# Sheet1.net
KiCad netlist of a schematic drawn in Altium Designer
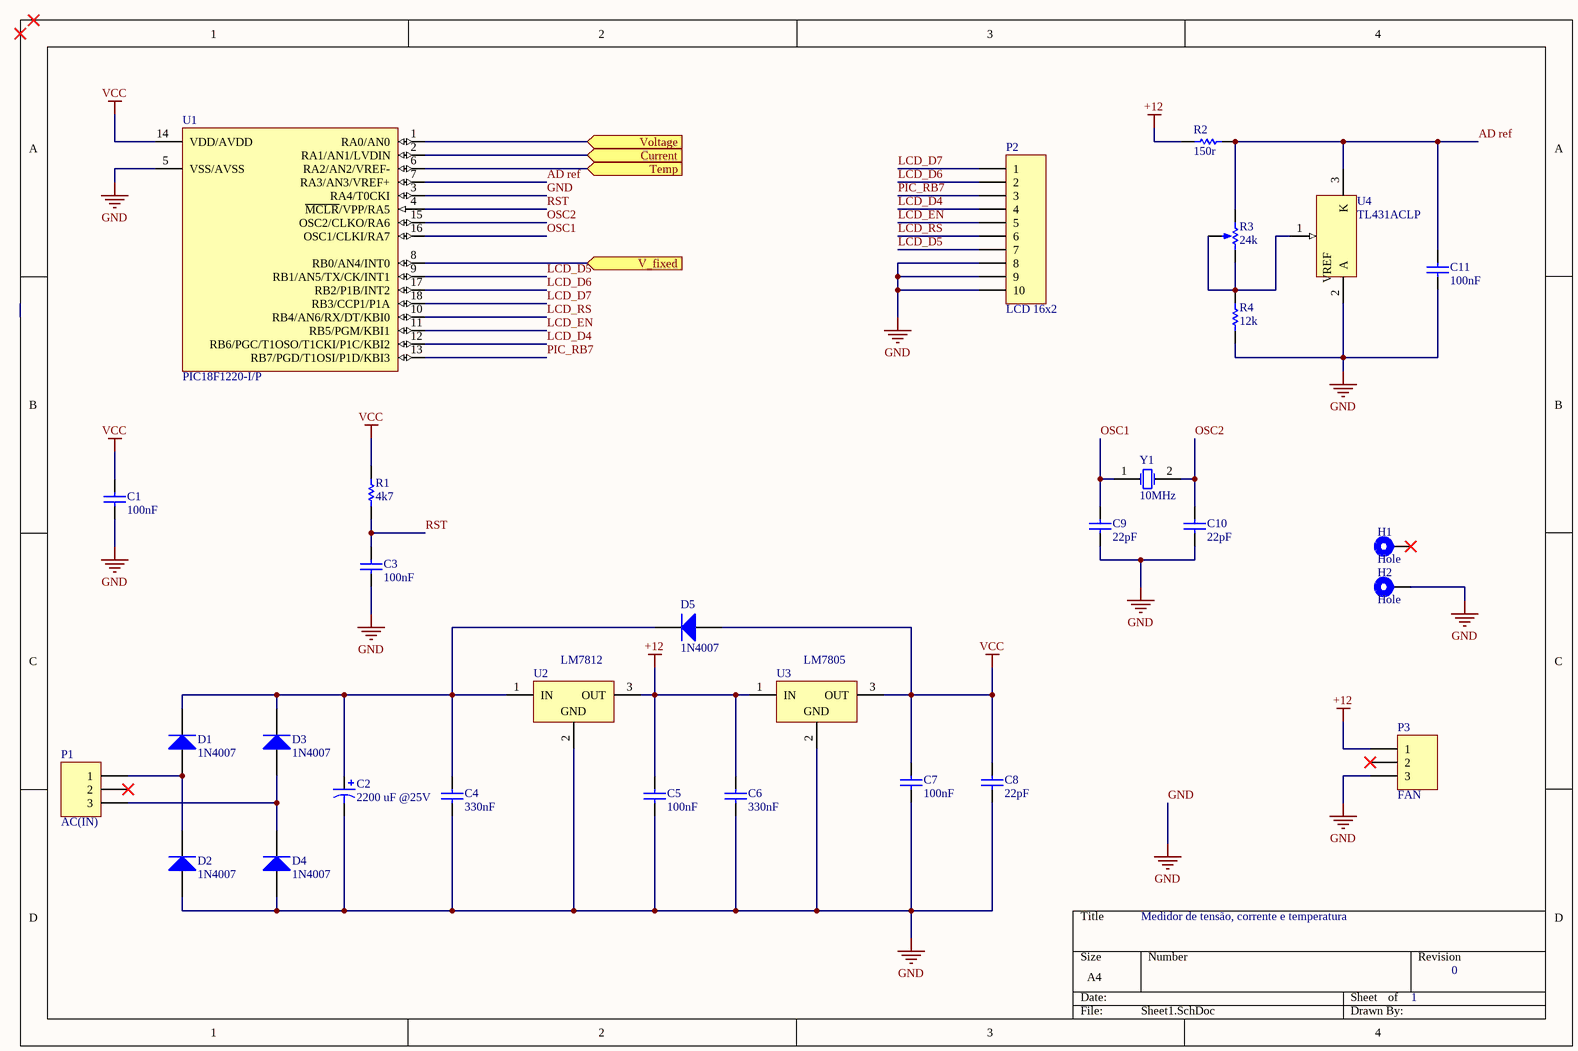
[diagram p0: Sheet1.SchDoc]

(export (version "E")
  (design (tool "Eeschema 10.0.6"))
  (components
    (comp (ref "C1")
      (value "100nF")
      (footprint "RAD-0.2")
      (description "Capacitor")
      (libsource (lib "Basic Library") (part "C"))
    )
    (comp (ref "C2")
      (value "2200 uF @25V")
      (footprint "CAPPR5-13x21")
      (description "Polarized Capacitor")
      (libsource (lib "Basic Library") (part "CP"))
    )
    (comp (ref "C3")
      (value "100nF")
      (footprint "RAD-0.2")
      (description "Capacitor")
      (libsource (lib "Basic Library") (part "C"))
    )
    (comp (ref "C4")
      (value "330nF")
      (footprint "RAD-0.2")
      (description "Capacitor")
      (libsource (lib "Basic Library") (part "C"))
    )
    (comp (ref "C5")
      (value "100nF")
      (footprint "RAD-0.2")
      (description "Capacitor")
      (libsource (lib "Basic Library") (part "C"))
    )
    (comp (ref "C6")
      (value "330nF")
      (footprint "RAD-0.2")
      (description "Capacitor")
      (libsource (lib "Basic Library") (part "C"))
    )
    (comp (ref "C7")
      (value "100nF")
      (footprint "RAD-0.2")
      (description "Capacitor")
      (libsource (lib "Basic Library") (part "C"))
    )
    (comp (ref "C8")
      (value "22pF")
      (footprint "RAD-0.2")
      (description "Capacitor")
      (libsource (lib "Basic Library") (part "C"))
    )
    (comp (ref "C9")
      (value "22pF")
      (footprint "RAD-0.2")
      (description "Capacitor")
      (libsource (lib "Basic Library") (part "C"))
    )
    (comp (ref "C10")
      (value "22pF")
      (footprint "RAD-0.2")
      (description "Capacitor")
      (libsource (lib "Basic Library") (part "C"))
    )
    (comp (ref "C11")
      (value "100nF")
      (footprint "RAD-0.2")
      (description "Capacitor")
      (libsource (lib "Basic Library") (part "C"))
    )
    (comp (ref "D1")
      (value "1N4007")
      (footprint "DIODE-1N400X")
      (description "Diode")
      (libsource (lib "Basic Library") (part "D"))
    )
    (comp (ref "D2")
      (value "1N4007")
      (footprint "DIODE-1N400X")
      (description "Diode")
      (libsource (lib "Basic Library") (part "D"))
    )
    (comp (ref "D3")
      (value "1N4007")
      (footprint "DIODE-1N400X")
      (description "Diode")
      (libsource (lib "Basic Library") (part "D"))
    )
    (comp (ref "D4")
      (value "1N4007")
      (footprint "DIODE-1N400X")
      (description "Diode")
      (libsource (lib "Basic Library") (part "D"))
    )
    (comp (ref "D5")
      (value "1N4007")
      (footprint "DO-41")
      (description "1 Amp General Purpose Rectifier")
      (fields (field (name "PUBLISHER") "Altium Limited"))
      (libsource (lib "Miscellaneous Devices") (part "Diode 1N4007"))
    )
    (comp (ref "H1") (value "Hole") (footprint "HOLE_M3") (libsource (lib "Basic Library") (part "Hole")))
    (comp (ref "H2") (value "Hole") (footprint "HOLE_M3") (libsource (lib "Basic Library") (part "Hole")))
    (comp (ref "P1")
      (value "AC(IN)")
      (footprint "HDR1X3")
      (description "Header, 3-Pin")
      (fields (field (name "PUBLISHER") "Altium Limited"))
      (libsource (lib "") (part "Header 3_1"))
    )
    (comp (ref "P2")
      (value "LCD 16x2")
      (footprint "HDR1X10")
      (description "Header, 10-Pin")
      (fields (field (name "PUBLISHER") "Altium Limited"))
      (libsource (lib "Miscellaneous Connectors") (part "Header 10"))
    )
    (comp (ref "P3")
      (value "FAN")
      (footprint "HDR1X3")
      (description "Header, 3-Pin")
      (fields (field (name "PUBLISHER") "Altium Limited"))
      (libsource (lib "Miscellaneous Connectors") (part "Header 3"))
    )
    (comp (ref "R1")
      (value "4k7")
      (footprint "AXIAL-0.4")
      (description "Resistor")
      (libsource (lib "Basic Library") (part "R"))
    )
    (comp (ref "R2")
      (value "150r")
      (footprint "AXIAL-0.4")
      (description "Resistor")
      (libsource (lib "Basic Library") (part "R"))
    )
    (comp (ref "R3")
      (value "24k")
      (footprint "VR1")
      (description "Potentiometer")
      (libsource (lib "Basic Library") (part "R Pot"))
    )
    (comp (ref "R4")
      (value "12k")
      (footprint "AXIAL-0.4")
      (description "Resistor")
      (libsource (lib "Basic Library") (part "R"))
    )
    (comp (ref "U1")
      (value "PIC18F1220-I/P")
      (footprint "PDIP300-P18")
      (fields (field (name "PUBLISHER") "Altium Limited"))
      (libsource (lib "Microchip Microcontroller 8-Bit PIC18") (part "PIC18F1220-I/P"))
    )
    (comp (ref "U2")
      (value "LM7812")
      (footprint "T03B")
      (description "Series 3-Terminal Positive Regulators, 3-pin TO-220")
      (fields
        (field (name "PARTNUMBER") "LM7808CT")
        (field (name "MANUFACTURER") "National Semiconductor")
        (field (name "PUBLISHER") "Altium Limited")
      )
      (libsource (lib "NSC Legacy") (part "LM7808CT"))
    )
    (comp (ref "U3")
      (value "LM7805")
      (footprint "T03B")
      (description "Series 3-Terminal Positive Regulators, 3-pin TO-220")
      (fields
        (field (name "PARTNUMBER") "LM7808CT")
        (field (name "MANUFACTURER") "National Semiconductor")
        (field (name "PUBLISHER") "Altium Limited")
      )
      (libsource (lib "NSC Legacy") (part "LM7808CT"))
    )
    (comp (ref "U4")
      (value "TL431ACLP")
      (footprint "LP03")
      (description "Adjustable Precision Shunt Regulator")
      (fields (field (name "PUBLISHER") "Altium Limited"))
      (libsource (lib "TI Power Mgt Voltage Regulator") (part "TL431ACLP"))
    )
    (comp (ref "Y1")
      (value "10MHz")
      (footprint "CRYSTAL-HC49S")
      (description "Crystal Oscillator")
      (libsource (lib "Basic Library") (part "XTAL"))
    )
  )
  (nets
    (net (code "1") (name "+12") (class "Default")
      (node (ref "C5") (pin "1") (pinfunction "1_1") (pintype "passive"))
      (node (ref "C6") (pin "1") (pinfunction "1_1") (pintype "passive"))
      (node (ref "P3") (pin "1") (pinfunction "1_1") (pintype "passive"))
      (node (ref "R2") (pin "1") (pinfunction "1_1") (pintype "passive"))
      (node (ref "U2") (pin "3") (pinfunction "OUT_3") (pintype "power_in"))
      (node (ref "U3") (pin "1") (pinfunction "IN_1") (pintype "power_in"))
    )
    (net (code "2") (name "/AD ref") (class "Default")
      (node (ref "C11") (pin "1") (pinfunction "1_1") (pintype "passive"))
      (node (ref "R2") (pin "2") (pinfunction "2_2") (pintype "passive"))
      (node (ref "R3") (pin "1") (pinfunction "TOP_1") (pintype "passive"))
      (node (ref "U1") (pin "7") (pinfunction "RA3/AN3/VREF+_7") (pintype "bidirectional"))
      (node (ref "U4") (pin "3") (pinfunction "K_3") (pintype "power_in"))
    )
    (net (code "3") (name "/Current") (class "Default")
      (node (ref "U1") (pin "2") (pinfunction "RA1/AN1/LVDIN_2") (pintype "bidirectional"))
    )
    (net (code "4") (name "/LCD_D4") (class "Default")
      (node (ref "P2") (pin "4") (pinfunction "4_4") (pintype "passive"))
      (node (ref "U1") (pin "12") (pinfunction "RB6/PGC/T1OSO/T1CKI/P1C/KBI2_12") (pintype "bidirectional"))
    )
    (net (code "5") (name "/LCD_D5") (class "Default")
      (node (ref "P2") (pin "7") (pinfunction "7_7") (pintype "passive"))
      (node (ref "U1") (pin "9") (pinfunction "RB1/AN5/TX/CK/INT1_9") (pintype "bidirectional"))
    )
    (net (code "6") (name "/LCD_D6") (class "Default")
      (node (ref "P2") (pin "2") (pinfunction "2_2") (pintype "passive"))
      (node (ref "U1") (pin "17") (pinfunction "RB2/P1B/INT2_17") (pintype "bidirectional"))
    )
    (net (code "7") (name "/LCD_D7") (class "Default")
      (node (ref "P2") (pin "1") (pinfunction "1_1") (pintype "passive"))
      (node (ref "U1") (pin "18") (pinfunction "RB3/CCP1/P1A_18") (pintype "bidirectional"))
    )
    (net (code "8") (name "/LCD_EN") (class "Default")
      (node (ref "P2") (pin "5") (pinfunction "5_5") (pintype "passive"))
      (node (ref "U1") (pin "11") (pinfunction "RB5/PGM/KBI1_11") (pintype "bidirectional"))
    )
    (net (code "9") (name "/LCD_RS") (class "Default")
      (node (ref "P2") (pin "6") (pinfunction "6_6") (pintype "passive"))
      (node (ref "U1") (pin "10") (pinfunction "RB4/AN6/RX/DT/KBI0_10") (pintype "bidirectional"))
    )
    (net (code "10") (name "/OSC1") (class "Default")
      (node (ref "C9") (pin "2") (pinfunction "2_2") (pintype "passive"))
      (node (ref "U1") (pin "16") (pinfunction "OSC1/CLKI/RA7_16") (pintype "bidirectional"))
      (node (ref "Y1") (pin "1") (pinfunction "OSC1_1") (pintype "passive"))
    )
    (net (code "11") (name "/OSC2") (class "Default")
      (node (ref "C10") (pin "2") (pinfunction "2_2") (pintype "passive"))
      (node (ref "U1") (pin "15") (pinfunction "OSC2/CLKO/RA6_15") (pintype "bidirectional"))
      (node (ref "Y1") (pin "2") (pinfunction "OSC2_2") (pintype "passive"))
    )
    (net (code "12") (name "/PIC_RB7") (class "Default")
      (node (ref "P2") (pin "3") (pinfunction "3_3") (pintype "passive"))
      (node (ref "U1") (pin "13") (pinfunction "RB7/PGD/T1OSI/P1D/KBI3_13") (pintype "bidirectional"))
    )
    (net (code "13") (name "/RST") (class "Default")
      (node (ref "C3") (pin "1") (pinfunction "1_1") (pintype "passive"))
      (node (ref "R1") (pin "1") (pinfunction "1_1") (pintype "passive"))
      (node (ref "U1") (pin "4") (pinfunction "~{MCLR}/VPP/RA5_4") (pintype "input"))
    )
    (net (code "14") (name "/Temp") (class "Default")
      (node (ref "U1") (pin "6") (pinfunction "RA2/AN2/VREF-_6") (pintype "bidirectional"))
    )
    (net (code "15") (name "/V_fixed") (class "Default")
      (node (ref "U1") (pin "8") (pinfunction "RB0/AN4/INT0_8") (pintype "bidirectional"))
    )
    (net (code "16") (name "/Voltage") (class "Default")
      (node (ref "U1") (pin "1") (pinfunction "RA0/AN0_1") (pintype "bidirectional"))
    )
    (net (code "17") (name "GND") (class "Default")
      (node (ref "C1") (pin "2") (pinfunction "2_2") (pintype "passive"))
      (node (ref "C10") (pin "1") (pinfunction "1_1") (pintype "passive"))
      (node (ref "C11") (pin "2") (pinfunction "2_2") (pintype "passive"))
      (node (ref "C2") (pin "2") (pinfunction "2_2") (pintype "passive"))
      (node (ref "C3") (pin "2") (pinfunction "2_2") (pintype "passive"))
      (node (ref "C4") (pin "2") (pinfunction "2_2") (pintype "passive"))
      (node (ref "C5") (pin "2") (pinfunction "2_2") (pintype "passive"))
      (node (ref "C6") (pin "2") (pinfunction "2_2") (pintype "passive"))
      (node (ref "C7") (pin "2") (pinfunction "2_2") (pintype "passive"))
      (node (ref "C8") (pin "1") (pinfunction "1_1") (pintype "passive"))
      (node (ref "C9") (pin "1") (pinfunction "1_1") (pintype "passive"))
      (node (ref "D2") (pin "1") (pinfunction "A_1") (pintype "passive"))
      (node (ref "D4") (pin "1") (pinfunction "A_1") (pintype "passive"))
      (node (ref "H2") (pin "1") (pinfunction "1_1") (pintype "passive"))
      (node (ref "P2") (pin "10") (pinfunction "10_10") (pintype "passive"))
      (node (ref "P2") (pin "8") (pinfunction "8_8") (pintype "passive"))
      (node (ref "P2") (pin "9") (pinfunction "9_9") (pintype "passive"))
      (node (ref "P3") (pin "3") (pinfunction "3_3") (pintype "passive"))
      (node (ref "R4") (pin "1") (pinfunction "1_1") (pintype "passive"))
      (node (ref "U1") (pin "3") (pinfunction "RA4/T0CKI_3") (pintype "bidirectional"))
      (node (ref "U1") (pin "5") (pinfunction "VSS/AVSS_5") (pintype "power_in"))
      (node (ref "U2") (pin "2") (pinfunction "GND_2") (pintype "power_in"))
      (node (ref "U3") (pin "2") (pinfunction "GND_2") (pintype "power_in"))
      (node (ref "U4") (pin "2") (pinfunction "A_2") (pintype "power_in"))
    )
    (net (code "18") (name "Net-(D1-A)") (class "Default")
      (node (ref "D1") (pin "1") (pinfunction "A_1") (pintype "passive"))
      (node (ref "D2") (pin "2") (pinfunction "K_2") (pintype "passive"))
      (node (ref "P1") (pin "1") (pinfunction "1_1") (pintype "passive"))
    )
    (net (code "19") (name "Net-(D1-K)") (class "Default")
      (node (ref "C2") (pin "1") (pinfunction "1_1") (pintype "passive"))
      (node (ref "C4") (pin "1") (pinfunction "1_1") (pintype "passive"))
      (node (ref "D1") (pin "2") (pinfunction "K_2") (pintype "passive"))
      (node (ref "D3") (pin "2") (pinfunction "K_2") (pintype "passive"))
      (node (ref "D5") (pin "2") (pinfunction "K_2") (pintype "passive"))
      (node (ref "U2") (pin "1") (pinfunction "IN_1") (pintype "power_in"))
    )
    (net (code "20") (name "Net-(D3-A)") (class "Default")
      (node (ref "D3") (pin "1") (pinfunction "A_1") (pintype "passive"))
      (node (ref "D4") (pin "2") (pinfunction "K_2") (pintype "passive"))
      (node (ref "P1") (pin "3") (pinfunction "3_3") (pintype "passive"))
    )
    (net (code "21") (name "Net-(R3-BOT)") (class "Default")
      (node (ref "R3") (pin "2") (pinfunction "BOT_2") (pintype "passive"))
      (node (ref "R3") (pin "3") (pinfunction "TAP_3") (pintype "passive"))
      (node (ref "R4") (pin "2") (pinfunction "2_2") (pintype "passive"))
      (node (ref "U4") (pin "1") (pinfunction "VREF_1") (pintype "input"))
    )
    (net (code "22") (name "VCC") (class "Default")
      (node (ref "C1") (pin "1") (pinfunction "1_1") (pintype "passive"))
      (node (ref "C7") (pin "1") (pinfunction "1_1") (pintype "passive"))
      (node (ref "C8") (pin "2") (pinfunction "2_2") (pintype "passive"))
      (node (ref "D5") (pin "1") (pinfunction "A_1") (pintype "passive"))
      (node (ref "R1") (pin "2") (pinfunction "2_2") (pintype "passive"))
      (node (ref "U1") (pin "14") (pinfunction "VDD/AVDD_14") (pintype "power_in"))
      (node (ref "U3") (pin "3") (pinfunction "OUT_3") (pintype "power_in"))
    )
    (net (code "23") (name "unconnected-(H1-Pad1)") (class "Default")
      (node (ref "H1") (pin "1") (pinfunction "1_1") (pintype "passive+no_connect"))
    )
    (net (code "24") (name "unconnected-(P1-Pad2)") (class "Default")
      (node (ref "P1") (pin "2") (pinfunction "2_2") (pintype "passive+no_connect"))
    )
    (net (code "25") (name "unconnected-(P3-Pad2)") (class "Default")
      (node (ref "P3") (pin "2") (pinfunction "2_2") (pintype "passive+no_connect"))
    )
  )
)
